# DC-Link_Shutdown_Circuit.net
KiCad netlist of a schematic drawn in Altium Designer
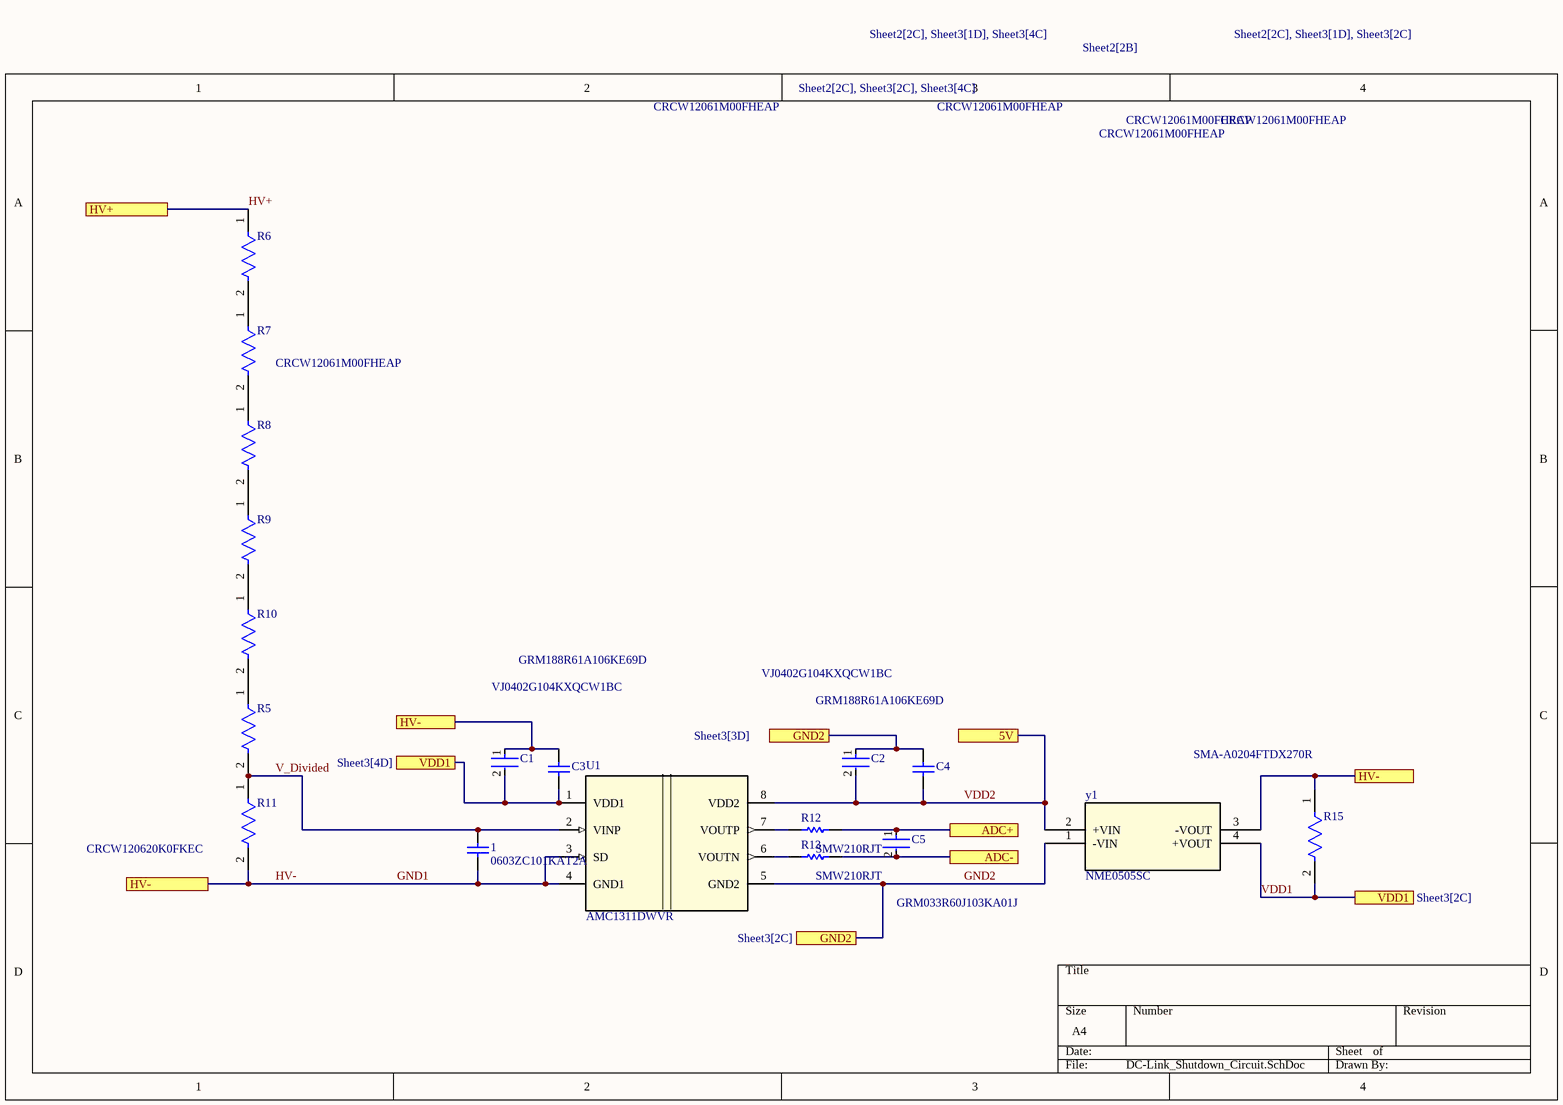
[diagram p0: DC-Link_Shutdown_Circuit.SchDoc]

(export (version "E")
  (design (tool "Eeschema 10.0.6"))
  (components
    (comp (ref "1")
      (value "0603ZC101KAT2A")
      (footprint "CAPC1608X90X35LL15T15")
      (fields (field (name "MANUFACTURER") "AVX Interconnect / Elco"))
      (libsource (lib "Altium Content Vault") (part "CAP"))
    )
    (comp (ref "C1")
      (value "GRM188R61A106KE69D")
      (footprint "FP-GRM18-0_15-MFG")
      (description "CAP CER 10UF 10V X5R 0603")
      (fields
        (field (name "OCTOPART") "https://octopart.com/grm188r61a106ke69d-murata-22851381")
        (field (name "MANUFACTURER") "Murata")
      )
      (libsource (lib "Altium Content Vault") (part "11868f565c42a9108669ba33697ecf6"))
    )
    (comp (ref "C2")
      (value "GRM188R61A106KE69D")
      (footprint "FP-GRM18-0_15-MFG")
      (description "CAP CER 10UF 10V X5R 0603")
      (fields
        (field (name "OCTOPART") "https://octopart.com/grm188r61a106ke69d-murata-22851381")
        (field (name "MANUFACTURER") "Murata")
      )
      (libsource (lib "Altium Content Vault") (part "11868f565c42a9108669ba33697ecf6"))
    )
    (comp (ref "C3")
      (value "VJ0402G104KXQCW1BC")
      (footprint "CAPC1005X55X25ML05T10")
      (fields (field (name "MANUFACTURER") "Vitramon"))
      (libsource (lib "Altium Content Vault") (part "CAP"))
    )
    (comp (ref "C4")
      (value "VJ0402G104KXQCW1BC")
      (footprint "CAPC1005X55X25ML05T10")
      (fields (field (name "MANUFACTURER") "Vitramon"))
      (libsource (lib "Altium Content Vault") (part "CAP"))
    )
    (comp (ref "C5")
      (value "GRM033R60J103KA01J")
      (footprint "FP-GRM033-0_03-IPC_B")
      (description "Chip Multilayer Ceramic Capacitors for General Purpose, 0201, 10000pF, X5R, 15%, 10%, 6.3V")
      (libsource (lib "Altium Content Vault") (part "b4654b650e69147ec39a6b967a45e02"))
    )
    (comp (ref "R5")
      (value "CRCW12061M00FHEAP")
      (footprint "FP-CRCW1206-Pe3-IPC_C")
      (description "RES Thick Film, 1MΩ, 1%, 0.25W, 50ppm/°C, 1206")
      (fields (field (name "TOLERANCE") "1%"))
      (libsource (lib "Altium Content Vault") (part "1029c3af85768c4190bb7ad29bc67b5"))
    )
    (comp (ref "R6")
      (value "CRCW12061M00FHEAP")
      (footprint "FP-CRCW1206-Pe3-IPC_C")
      (description "RES Thick Film, 1MΩ, 1%, 0.25W, 50ppm/°C, 1206")
      (fields (field (name "TOLERANCE") "1%"))
      (libsource (lib "Altium Content Vault") (part "1029c3af85768c4190bb7ad29bc67b5"))
    )
    (comp (ref "R7")
      (value "CRCW12061M00FHEAP")
      (footprint "FP-CRCW1206-Pe3-IPC_C")
      (description "RES Thick Film, 1MΩ, 1%, 0.25W, 50ppm/°C, 1206")
      (fields (field (name "TOLERANCE") "1%"))
      (libsource (lib "Altium Content Vault") (part "1029c3af85768c4190bb7ad29bc67b5"))
    )
    (comp (ref "R8")
      (value "CRCW12061M00FHEAP")
      (footprint "FP-CRCW1206-Pe3-IPC_C")
      (description "RES Thick Film, 1MΩ, 1%, 0.25W, 50ppm/°C, 1206")
      (fields (field (name "TOLERANCE") "1%"))
      (libsource (lib "Altium Content Vault") (part "1029c3af85768c4190bb7ad29bc67b5"))
    )
    (comp (ref "R9")
      (value "CRCW12061M00FHEAP")
      (footprint "FP-CRCW1206-Pe3-IPC_C")
      (description "RES Thick Film, 1MΩ, 1%, 0.25W, 50ppm/°C, 1206")
      (fields (field (name "TOLERANCE") "1%"))
      (libsource (lib "Altium Content Vault") (part "1029c3af85768c4190bb7ad29bc67b5"))
    )
    (comp (ref "R10")
      (value "CRCW12061M00FHEAP")
      (footprint "FP-CRCW1206-Pe3-IPC_C")
      (description "RES Thick Film, 1MΩ, 1%, 0.25W, 50ppm/°C, 1206")
      (fields (field (name "TOLERANCE") "1%"))
      (libsource (lib "Altium Content Vault") (part "1029c3af85768c4190bb7ad29bc67b5"))
    )
    (comp (ref "R11")
      (value "CRCW120620K0FKEC")
      (footprint "FP-CRCW1206-e3-MFG")
      (description "RES Thick Film, 20kΩ, 1%, 0.25W, 100ppm/°C, 1206")
      (fields (field (name "TOLERANCE") "1%"))
      (libsource (lib "Altium Content Vault") (part "1029c3af85768c4190bb7ad29bc67b5"))
    )
    (comp (ref "R12")
      (value "SMW210RJT")
      (footprint "TECO-SMW2-2_V")
      (description "Moulded Power Resistor, 2 W, 10 Ohm +/- 5%, 2-Pin 6.7 x 4 x 3.85 mm SMD, RoHS, Tape and Reel")
      (fields (field (name "TOLERANCE") "+/- 5%") (field (name "MANUFACTURER") "TE Connectivity"))
      (libsource (lib "Altium Content Vault") (part "TECO-SMW-2"))
    )
    (comp (ref "R13")
      (value "SMW210RJT")
      (footprint "TECO-SMW2-2_V")
      (description "Moulded Power Resistor, 2 W, 10 Ohm +/- 5%, 2-Pin 6.7 x 4 x 3.85 mm SMD, RoHS, Tape and Reel")
      (fields (field (name "TOLERANCE") "+/- 5%") (field (name "MANUFACTURER") "TE Connectivity"))
      (libsource (lib "Altium Content Vault") (part "TECO-SMW-2"))
    )
    (comp (ref "R15")
      (value "SMA-A0204FTDX270R")
      (footprint "FP-SMA-A0204-MFG")
      (description "SMA-A 0204 270Ω 0.4W 50ppm/ºC 1.00% 200V")
      (fields
        (field (name "OCTOPART") "https://octopart.com/sma-a0204ftdx270r-te+connectivity-89729412")
        (field (name "TOLERANCE") "0.01")
      )
      (libsource (lib "Altium Content Vault") (part "1029c3af85768c4190bb7ad29bc67b5"))
    )
    (comp (ref "U1")
      (value "AMC1311DWVR")
      (footprint "DWV0008A")
      (description "2-V input, precision voltage sensing reinforced isolated amplifier 8-SOIC -40 to 125")
      (fields (field (name "COPYRIGHT") "Copyright (C) 2025 Ultra Librarian. All rights reserved."))
      (libsource (lib "Alt_ium Course") (part "AMC1311DWVR"))
    )
    (comp (ref "y1")
      (value "NME0505SC")
      (footprint "SIP04_NME_11P53X6P1_MUR")
      (description "Description")
      (fields (field (name "COPYRIGHT") "Copyright (C) 2025 Ultra Librarian. All rights reserved."))
      (libsource (lib "Alt_ium Course") (part "NME0505SC"))
    )
  )
  (nets
    (net (code "1") (name "/ADC+") (class "Default")
      (node (ref "C5") (pin "1") (pinfunction "1_1") (pintype "passive"))
      (node (ref "R12") (pin "2") (pinfunction "2_2") (pintype "passive"))
    )
    (net (code "2") (name "/ADC-") (class "Default")
      (node (ref "C5") (pin "2") (pinfunction "2_2") (pintype "passive"))
      (node (ref "R13") (pin "2") (pinfunction "2_2") (pintype "passive"))
    )
    (net (code "3") (name "/GND1") (class "Default")
      (node (ref "1") (pin "2") (pinfunction "2_2") (pintype "passive"))
      (node (ref "C1") (pin "1") (pinfunction "1_1") (pintype "passive"))
      (node (ref "C3") (pin "1") (pinfunction "1_1") (pintype "passive"))
      (node (ref "R11") (pin "2") (pinfunction "2_2") (pintype "passive"))
      (node (ref "R15") (pin "1") (pinfunction "1_1") (pintype "passive"))
      (node (ref "U1") (pin "3") (pinfunction "SD_3") (pintype "input"))
      (node (ref "U1") (pin "4") (pinfunction "GND1_4") (pintype "power_in"))
      (node (ref "y1") (pin "3") (pinfunction "-VOUT_3") (pintype "passive"))
    )
    (net (code "4") (name "/GND2") (class "Default")
      (node (ref "C2") (pin "1") (pinfunction "1_1") (pintype "passive"))
      (node (ref "C4") (pin "1") (pinfunction "1_1") (pintype "passive"))
      (node (ref "U1") (pin "5") (pinfunction "GND2_5") (pintype "power_in"))
      (node (ref "y1") (pin "1") (pinfunction "-VIN_1") (pintype "passive"))
    )
    (net (code "5") (name "/HV+") (class "Default")
      (node (ref "R6") (pin "1") (pinfunction "1_1") (pintype "passive"))
    )
    (net (code "6") (name "/VDD1") (class "Default")
      (node (ref "C1") (pin "2") (pinfunction "2_2") (pintype "passive"))
      (node (ref "C3") (pin "2") (pinfunction "2_2") (pintype "passive"))
      (node (ref "R15") (pin "2") (pinfunction "2_2") (pintype "passive"))
      (node (ref "U1") (pin "1") (pinfunction "VDD1_1") (pintype "power_in"))
      (node (ref "y1") (pin "4") (pinfunction "+VOUT_4") (pintype "passive"))
    )
    (net (code "7") (name "/VDD2") (class "Default")
      (node (ref "C2") (pin "2") (pinfunction "2_2") (pintype "passive"))
      (node (ref "C4") (pin "2") (pinfunction "2_2") (pintype "passive"))
      (node (ref "U1") (pin "8") (pinfunction "VDD2_8") (pintype "power_in"))
      (node (ref "y1") (pin "2") (pinfunction "+VIN_2") (pintype "passive"))
    )
    (net (code "8") (name "/V_Divided") (class "Default")
      (node (ref "1") (pin "1") (pinfunction "1_1") (pintype "passive"))
      (node (ref "R11") (pin "1") (pinfunction "1_1") (pintype "passive"))
      (node (ref "R5") (pin "2") (pinfunction "2_2") (pintype "passive"))
      (node (ref "U1") (pin "2") (pinfunction "VINP_2") (pintype "input"))
    )
    (net (code "9") (name "Net-(R6-Pad2)") (class "Default")
      (node (ref "R6") (pin "2") (pinfunction "2_2") (pintype "passive"))
      (node (ref "R7") (pin "1") (pinfunction "1_1") (pintype "passive"))
    )
    (net (code "10") (name "Net-(R7-Pad2)") (class "Default")
      (node (ref "R7") (pin "2") (pinfunction "2_2") (pintype "passive"))
      (node (ref "R8") (pin "1") (pinfunction "1_1") (pintype "passive"))
    )
    (net (code "11") (name "Net-(R8-Pad2)") (class "Default")
      (node (ref "R8") (pin "2") (pinfunction "2_2") (pintype "passive"))
      (node (ref "R9") (pin "1") (pinfunction "1_1") (pintype "passive"))
    )
    (net (code "12") (name "Net-(R10-Pad1)") (class "Default")
      (node (ref "R10") (pin "1") (pinfunction "1_1") (pintype "passive"))
      (node (ref "R9") (pin "2") (pinfunction "2_2") (pintype "passive"))
    )
    (net (code "13") (name "Net-(R10-Pad2)") (class "Default")
      (node (ref "R10") (pin "2") (pinfunction "2_2") (pintype "passive"))
      (node (ref "R5") (pin "1") (pinfunction "1_1") (pintype "passive"))
    )
    (net (code "14") (name "Net-(U1-VOUTN)") (class "Default")
      (node (ref "R13") (pin "1") (pinfunction "1_1") (pintype "passive"))
      (node (ref "U1") (pin "6") (pinfunction "VOUTN_6") (pintype "output"))
    )
    (net (code "15") (name "Net-(U1-VOUTP)") (class "Default")
      (node (ref "R12") (pin "1") (pinfunction "1_1") (pintype "passive"))
      (node (ref "U1") (pin "7") (pinfunction "VOUTP_7") (pintype "output"))
    )
  )
)
